# holiday-candleholder.net
KiCad netlist of a schematic drawn in EAGLE
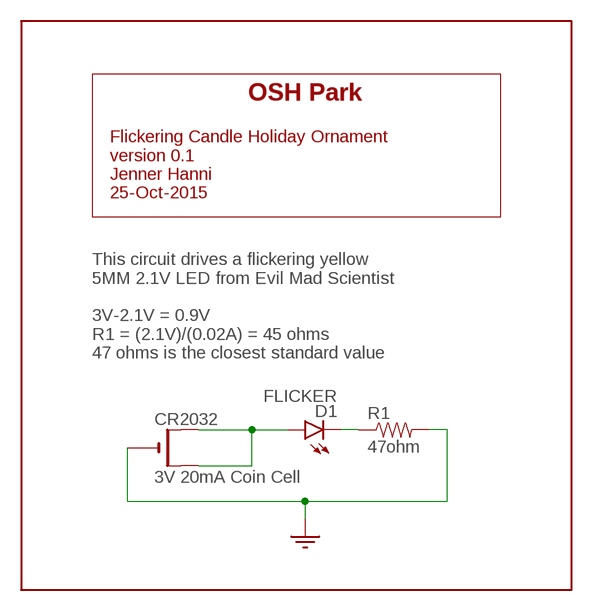
[diagram p0: schematic, sheet 1]

(export (version "E")
  (design (tool "Eeschema 10.0.6"))
  (components
    (comp (ref "CR2032")
      (value "3V 20mA Coin Cell")
      (footprint "eagle-import:CR2032-BATT-STRAP-MPD")
      (libsource (lib "eagle-import") (part "CR2032STRAP"))
    )
    (comp (ref "D1")
      (value "FLICKER")
      (footprint "eagle-import:LED5MM")
      (libsource (lib "eagle-import") (part "LED5MM"))
    )
    (comp (ref "R1")
      (value "47ohm")
      (footprint "eagle-import:RES-CF14-TH")
      (libsource (lib "eagle-import") (part "RESISTOR"))
    )
  )
  (nets
    (net (code "1") (name "GND") (class "Default")
      (node (ref "CR2032") (pin "-") (pinfunction "-_-") (pintype "passive"))
      (node (ref "R1") (pin "P$2") (pinfunction "2_P$2") (pintype "passive"))
    )
    (net (code "2") (name "Net-(CR2032-+)") (class "Default")
      (node (ref "CR2032") (pin "+$1") (pinfunction "+_+$1") (pintype "passive"))
      (node (ref "CR2032") (pin "+$2") (pinfunction "+1_+$2") (pintype "passive"))
      (node (ref "D1") (pin "A") (pinfunction "A_A") (pintype "passive"))
    )
    (net (code "3") (name "Net-(D1-C)") (class "Default")
      (node (ref "D1") (pin "K") (pinfunction "C_K") (pintype "passive"))
      (node (ref "R1") (pin "P$1") (pinfunction "1_P$1") (pintype "passive"))
    )
  )
)
